# MQ-135_Matheus_Rossetti_-_14205347.net
KiCad netlist of a schematic drawn in EAGLE
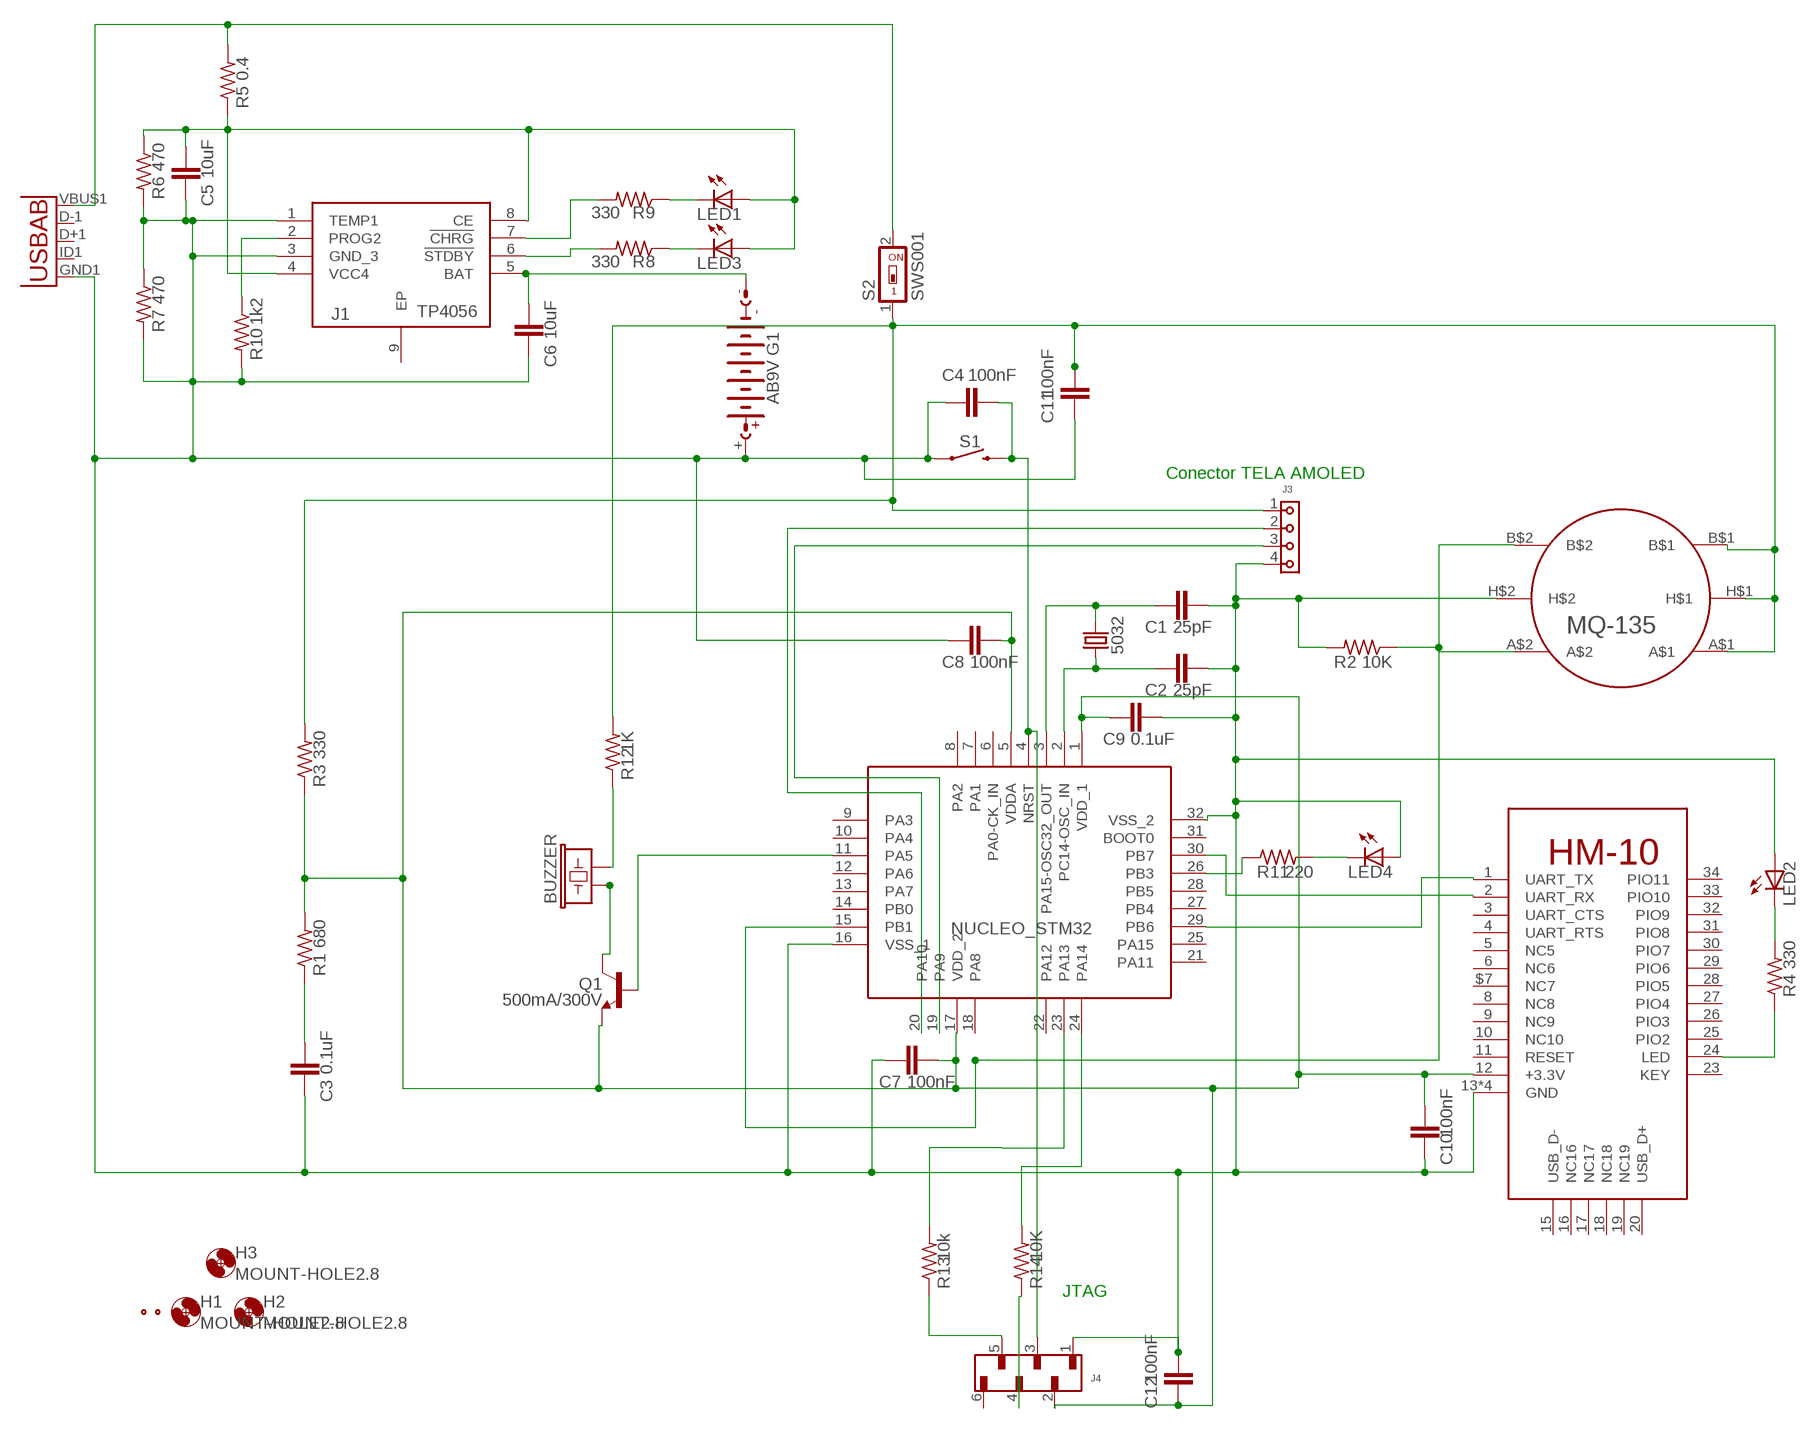
[diagram p0: schematic, sheet 1]

(export (version "E")
  (design (tool "Eeschema 10.0.6"))
  (components
    (comp (ref "BT_SENSOR")
      (value "HM-10-BOARD")
      (footprint "eagle-import:26.9X13X2.2_BOARD")
      (libsource (lib "eagle-import") (part "HM-10-BOARD"))
    )
    (comp (ref "C1")
      (value "25pF")
      (footprint "eagle-import:CAP_0805")
      (fields
        (field (name "DIGIKEY_PART_NUMBER") "311-1140-2-ND")
        (field (name "MANUFACTURER") "Yageo")
        (field (name "MPN") "CC0805KRX7R9BB104")
        (field (name "CREATED_BY") "PCBLayout.com")
      )
      (libsource (lib "eagle-import") (part "CC0805KRX7R9BB104"))
    )
    (comp (ref "C2")
      (value "25pF")
      (footprint "eagle-import:CAP_0805")
      (fields
        (field (name "DIGIKEY_PART_NUMBER") "311-1140-2-ND")
        (field (name "MANUFACTURER") "Yageo")
        (field (name "MPN") "CC0805KRX7R9BB104")
        (field (name "CREATED_BY") "PCBLayout.com")
      )
      (libsource (lib "eagle-import") (part "CC0805KRX7R9BB104"))
    )
    (comp (ref "C3")
      (value "0.1uF")
      (footprint "eagle-import:CAP_0805")
      (fields
        (field (name "DIGIKEY_PART_NUMBER") "311-1140-2-ND")
        (field (name "MANUFACTURER") "Yageo")
        (field (name "MPN") "CC0805KRX7R9BB104")
        (field (name "CREATED_BY") "PCBLayout.com")
      )
      (libsource (lib "eagle-import") (part "CC0805KRX7R9BB104"))
    )
    (comp (ref "C4")
      (value "100nF")
      (footprint "eagle-import:CAP_0805")
      (fields
        (field (name "DIGIKEY_PART_NUMBER") "311-1140-2-ND")
        (field (name "MANUFACTURER") "Yageo")
        (field (name "MPN") "CC0805KRX7R9BB104")
        (field (name "CREATED_BY") "PCBLayout.com")
      )
      (libsource (lib "eagle-import") (part "CC0805KRX7R9BB104"))
    )
    (comp (ref "C5")
      (value "10uF")
      (footprint "eagle-import:CAP_0805")
      (fields
        (field (name "DIGIKEY_PART_NUMBER") "311-1140-2-ND")
        (field (name "MANUFACTURER") "Yageo")
        (field (name "MPN") "CC0805KRX7R9BB104")
        (field (name "CREATED_BY") "PCBLayout.com")
      )
      (libsource (lib "eagle-import") (part "CC0805KRX7R9BB104"))
    )
    (comp (ref "C6")
      (value "10uF")
      (footprint "eagle-import:CAP_0805")
      (fields
        (field (name "DIGIKEY_PART_NUMBER") "311-1140-2-ND")
        (field (name "MANUFACTURER") "Yageo")
        (field (name "MPN") "CC0805KRX7R9BB104")
        (field (name "CREATED_BY") "PCBLayout.com")
      )
      (libsource (lib "eagle-import") (part "CC0805KRX7R9BB104"))
    )
    (comp (ref "C7")
      (value "100nF")
      (footprint "eagle-import:CAP_0805")
      (fields
        (field (name "DIGIKEY_PART_NUMBER") "311-1140-2-ND")
        (field (name "MANUFACTURER") "Yageo")
        (field (name "MPN") "CC0805KRX7R9BB104")
        (field (name "CREATED_BY") "PCBLayout.com")
      )
      (libsource (lib "eagle-import") (part "CC0805KRX7R9BB104"))
    )
    (comp (ref "C8")
      (value "100nF")
      (footprint "eagle-import:CAP_0805")
      (fields
        (field (name "DIGIKEY_PART_NUMBER") "311-1140-2-ND")
        (field (name "MANUFACTURER") "Yageo")
        (field (name "MPN") "CC0805KRX7R9BB104")
        (field (name "CREATED_BY") "PCBLayout.com")
      )
      (libsource (lib "eagle-import") (part "CC0805KRX7R9BB104"))
    )
    (comp (ref "C9")
      (value "0.1uF")
      (footprint "eagle-import:CAP_0805")
      (fields
        (field (name "DIGIKEY_PART_NUMBER") "311-1140-2-ND")
        (field (name "MANUFACTURER") "Yageo")
        (field (name "MPN") "CC0805KRX7R9BB104")
        (field (name "CREATED_BY") "PCBLayout.com")
      )
      (libsource (lib "eagle-import") (part "CC0805KRX7R9BB104"))
    )
    (comp (ref "C10")
      (value "100nF")
      (footprint "eagle-import:CAP_0805")
      (fields
        (field (name "DIGIKEY_PART_NUMBER") "311-1140-2-ND")
        (field (name "MANUFACTURER") "Yageo")
        (field (name "MPN") "CC0805KRX7R9BB104")
        (field (name "CREATED_BY") "PCBLayout.com")
      )
      (libsource (lib "eagle-import") (part "CC0805KRX7R9BB104"))
    )
    (comp (ref "C11")
      (value "100nF")
      (footprint "eagle-import:CAP_0805")
      (fields
        (field (name "DIGIKEY_PART_NUMBER") "311-1140-2-ND")
        (field (name "MANUFACTURER") "Yageo")
        (field (name "MPN") "CC0805KRX7R9BB104")
        (field (name "CREATED_BY") "PCBLayout.com")
      )
      (libsource (lib "eagle-import") (part "CC0805KRX7R9BB104"))
    )
    (comp (ref "C12")
      (value "100nF")
      (footprint "eagle-import:CAP_0805")
      (fields
        (field (name "DIGIKEY_PART_NUMBER") "311-1140-2-ND")
        (field (name "MANUFACTURER") "Yageo")
        (field (name "MPN") "CC0805KRX7R9BB104")
        (field (name "CREATED_BY") "PCBLayout.com")
      )
      (libsource (lib "eagle-import") (part "CC0805KRX7R9BB104"))
    )
    (comp (ref "G1")
      (value "AB9V")
      (footprint "eagle-import:AB9V")
      (libsource (lib "eagle-import") (part "AB9V"))
    )
    (comp (ref "H1")
      (value "MOUNT-HOLE2.8")
      (footprint "eagle-import:2,8")
      (libsource (lib "eagle-import") (part "MOUNT-HOLE2.8"))
    )
    (comp (ref "H2")
      (value "MOUNT-HOLE2.8")
      (footprint "eagle-import:2,8")
      (libsource (lib "eagle-import") (part "MOUNT-HOLE2.8"))
    )
    (comp (ref "H3")
      (value "MOUNT-HOLE2.8")
      (footprint "eagle-import:2,8")
      (libsource (lib "eagle-import") (part "MOUNT-HOLE2.8"))
    )
    (comp (ref "J1")
      (value "TP4056")
      (footprint "eagle-import:SOIC127P600X175-9N")
      (libsource (lib "eagle-import") (part "TP4056"))
    )
    (comp (ref "J3")
      (value "6130XX11821_61300411821")
      (footprint "eagle-import:61300411821")
      (libsource (lib "eagle-import") (part "6130XX11821_61300411821"))
    )
    (comp (ref "J4")
      (value "6100XX18221_61000618221")
      (footprint "eagle-import:61000618221")
      (libsource (lib "eagle-import") (part "6100XX18221_61000618221"))
    )
    (comp (ref "LED1")
      (value "LEDCHIP-LED0805")
      (footprint "eagle-import:CHIP-LED0805")
      (libsource (lib "eagle-import") (part "LEDCHIP-LED0805"))
    )
    (comp (ref "LED2")
      (value "LEDCHIP-LED0805")
      (footprint "eagle-import:CHIP-LED0805")
      (libsource (lib "eagle-import") (part "LEDCHIP-LED0805"))
    )
    (comp (ref "LED3")
      (value "LEDCHIP-LED0805")
      (footprint "eagle-import:CHIP-LED0805")
      (libsource (lib "eagle-import") (part "LEDCHIP-LED0805"))
    )
    (comp (ref "LED4")
      (value "LEDCHIP-LED0805")
      (footprint "eagle-import:CHIP-LED0805")
      (libsource (lib "eagle-import") (part "LEDCHIP-LED0805"))
    )
    (comp (ref "LS4")
      (value "BUZZER")
      (footprint "eagle-import:BUZZER-CCV-KIT")
      (libsource (lib "eagle-import") (part "BUZZER-SMD_KIT"))
    )
    (comp (ref "NUCLEO_STM32")
      (value "STM32")
      (footprint "eagle-import:QFP80P900X900X160-32N")
      (fields
        (field (name "ARROW_PART_NUMBER") "STM32L031K6T6TR")
        (field (name "MOUSER_PART_NUMBER") "511-STM32L031K6T6TR")
      )
      (libsource (lib "eagle-import") (part "STM32L031K6T6TR"))
    )
    (comp (ref "Q1")
      (value "500mA/300V")
      (footprint "eagle-import:SOT23-3")
      (libsource (lib "eagle-import") (part "TRANS_NPN-MMBTA42"))
    )
    (comp (ref "R1")
      (value "680")
      (footprint "eagle-import:RES_0805")
      (fields
        (field (name "DIGIKEY_PART_NUMBER") "541-0.0ATR-ND")
        (field (name "MANUFACTURER") "Vishay Dale")
        (field (name "MPN") "CRCW08050000Z0EA")
        (field (name "CREATED_BY") "PCBLayout.com")
      )
      (libsource (lib "eagle-import") (part "CRCW08050000Z0EA"))
    )
    (comp (ref "R2")
      (value "10K")
      (footprint "eagle-import:RES_0805")
      (fields
        (field (name "DIGIKEY_PART_NUMBER") "541-0.0ATR-ND")
        (field (name "MANUFACTURER") "Vishay Dale")
        (field (name "MPN") "CRCW08050000Z0EA")
        (field (name "CREATED_BY") "PCBLayout.com")
      )
      (libsource (lib "eagle-import") (part "CRCW08050000Z0EA"))
    )
    (comp (ref "R3")
      (value "330")
      (footprint "eagle-import:RES_0805")
      (fields
        (field (name "DIGIKEY_PART_NUMBER") "541-0.0ATR-ND")
        (field (name "MANUFACTURER") "Vishay Dale")
        (field (name "MPN") "CRCW08050000Z0EA")
        (field (name "CREATED_BY") "PCBLayout.com")
      )
      (libsource (lib "eagle-import") (part "CRCW08050000Z0EA"))
    )
    (comp (ref "R4")
      (value "330")
      (footprint "eagle-import:RES_0805")
      (fields
        (field (name "DIGIKEY_PART_NUMBER") "541-0.0ATR-ND")
        (field (name "MANUFACTURER") "Vishay Dale")
        (field (name "MPN") "CRCW08050000Z0EA")
        (field (name "CREATED_BY") "PCBLayout.com")
      )
      (libsource (lib "eagle-import") (part "CRCW08050000Z0EA"))
    )
    (comp (ref "R5")
      (value "0.4")
      (footprint "eagle-import:RES_0805")
      (fields
        (field (name "DIGIKEY_PART_NUMBER") "541-0.0ATR-ND")
        (field (name "MANUFACTURER") "Vishay Dale")
        (field (name "MPN") "CRCW08050000Z0EA")
        (field (name "CREATED_BY") "PCBLayout.com")
      )
      (libsource (lib "eagle-import") (part "CRCW08050000Z0EA"))
    )
    (comp (ref "R6")
      (value "470")
      (footprint "eagle-import:RES_0805")
      (fields
        (field (name "DIGIKEY_PART_NUMBER") "541-0.0ATR-ND")
        (field (name "MANUFACTURER") "Vishay Dale")
        (field (name "MPN") "CRCW08050000Z0EA")
        (field (name "CREATED_BY") "PCBLayout.com")
      )
      (libsource (lib "eagle-import") (part "CRCW08050000Z0EA"))
    )
    (comp (ref "R7")
      (value "470")
      (footprint "eagle-import:RES_0805")
      (fields
        (field (name "DIGIKEY_PART_NUMBER") "541-0.0ATR-ND")
        (field (name "MANUFACTURER") "Vishay Dale")
        (field (name "MPN") "CRCW08050000Z0EA")
        (field (name "CREATED_BY") "PCBLayout.com")
      )
      (libsource (lib "eagle-import") (part "CRCW08050000Z0EA"))
    )
    (comp (ref "R8")
      (value "330")
      (footprint "eagle-import:RES_0805")
      (fields
        (field (name "DIGIKEY_PART_NUMBER") "541-0.0ATR-ND")
        (field (name "MANUFACTURER") "Vishay Dale")
        (field (name "MPN") "CRCW08050000Z0EA")
        (field (name "SPICEPREFIX") "R")
        (field (name "CREATED_BY") "PCBLayout.com")
      )
      (libsource (lib "eagle-import") (part "CRCW08050000Z0EA"))
    )
    (comp (ref "R9")
      (value "330")
      (footprint "eagle-import:RES_0805")
      (fields
        (field (name "DIGIKEY_PART_NUMBER") "541-0.0ATR-ND")
        (field (name "MANUFACTURER") "Vishay Dale")
        (field (name "MPN") "CRCW08050000Z0EA")
        (field (name "SPICEPREFIX") "R")
        (field (name "CREATED_BY") "PCBLayout.com")
      )
      (libsource (lib "eagle-import") (part "CRCW08050000Z0EA"))
    )
    (comp (ref "R10")
      (value "1k2")
      (footprint "eagle-import:RES_0805")
      (fields
        (field (name "DIGIKEY_PART_NUMBER") "541-0.0ATR-ND")
        (field (name "MANUFACTURER") "Vishay Dale")
        (field (name "MPN") "CRCW08050000Z0EA")
        (field (name "CREATED_BY") "PCBLayout.com")
      )
      (libsource (lib "eagle-import") (part "CRCW08050000Z0EA"))
    )
    (comp (ref "R11")
      (value "220")
      (footprint "eagle-import:RES_0805")
      (fields
        (field (name "DIGIKEY_PART_NUMBER") "541-0.0ATR-ND")
        (field (name "MANUFACTURER") "Vishay Dale")
        (field (name "MPN") "CRCW08050000Z0EA")
        (field (name "CREATED_BY") "PCBLayout.com")
      )
      (libsource (lib "eagle-import") (part "CRCW08050000Z0EA"))
    )
    (comp (ref "R12")
      (value "1K")
      (footprint "eagle-import:RES_0805")
      (fields
        (field (name "DIGIKEY_PART_NUMBER") "541-0.0ATR-ND")
        (field (name "MANUFACTURER") "Vishay Dale")
        (field (name "MPN") "CRCW08050000Z0EA")
        (field (name "CREATED_BY") "PCBLayout.com")
      )
      (libsource (lib "eagle-import") (part "CRCW08050000Z0EA"))
    )
    (comp (ref "R13")
      (value "10k")
      (footprint "eagle-import:RES_0805")
      (fields
        (field (name "DIGIKEY_PART_NUMBER") "541-0.0ATR-ND")
        (field (name "MANUFACTURER") "Vishay Dale")
        (field (name "MPN") "CRCW08050000Z0EA")
        (field (name "CREATED_BY") "PCBLayout.com")
      )
      (libsource (lib "eagle-import") (part "CRCW08050000Z0EA"))
    )
    (comp (ref "R14")
      (value "10K")
      (footprint "eagle-import:RES_0805")
      (fields
        (field (name "DIGIKEY_PART_NUMBER") "541-0.0ATR-ND")
        (field (name "MANUFACTURER") "Vishay Dale")
        (field (name "MPN") "CRCW08050000Z0EA")
        (field (name "CREATED_BY") "PCBLayout.com")
      )
      (libsource (lib "eagle-import") (part "CRCW08050000Z0EA"))
    )
    (comp (ref "S1")
      (value "MOMENTARY-SWITCH-SPST-SMD-6.0X3.5MM")
      (footprint "eagle-import:TACTILE_SWITCH_SMD_6.0X3.5MM")
      (libsource (lib "eagle-import") (part "MOMENTARY-SWITCH-SPST-SMD-6.0X3.5MM"))
    )
    (comp (ref "S2")
      (value "SWS001")
      (footprint "eagle-import:SMS-001")
      (libsource (lib "eagle-import") (part "SWS001"))
    )
    (comp (ref "U$1")
      (value "MQ_135_A")
      (footprint "eagle-import:MQ-135")
      (libsource (lib "eagle-import") (part "MQ_135_A"))
    )
    (comp (ref "U1")
      (value "USB\"\"")
      (footprint "eagle-import:USB-MICRO-SMD")
      (libsource (lib "eagle-import") (part "USB{dblquote}{dblquote}"))
    )
    (comp (ref "X1")
      (value "FIDUCIAL_0.6-1.2MM")
      (footprint "eagle-import:FIDUCIAL0.6-1.2")
      (libsource (lib "eagle-import") (part "FIDUCIAL_0.6-1.2MM"))
    )
    (comp (ref "X2")
      (value "5032")
      (footprint "eagle-import:5032_2P")
      (fields
        (field (name "MANUFACTURER") "Xinhunjing")
        (field (name "MPN") "5032/2P")
        (field (name "CREATED_BY") "PCBLayout.com")
      )
      (libsource (lib "eagle-import") (part "5032/2P"))
    )
    (comp (ref "X3")
      (value "FIDUCIAL_0.6-1.2MM")
      (footprint "eagle-import:FIDUCIAL0.6-1.2")
      (libsource (lib "eagle-import") (part "FIDUCIAL_0.6-1.2MM"))
    )
  )
  (nets
    (net (code "1") (name "Net-(BT_SENSOR-+3.3V)") (class "Default")
      (node (ref "BT_SENSOR") (pin "12") (pinfunction "+3.3V_12") (pintype "bidirectional"))
      (node (ref "C10") (pin "1") (pinfunction "1_1") (pintype "passive"))
      (node (ref "C12") (pin "1") (pinfunction "1_1") (pintype "passive"))
      (node (ref "C7") (pin "1") (pinfunction "1_1") (pintype "passive"))
      (node (ref "C8") (pin "1") (pinfunction "1_1") (pintype "passive"))
      (node (ref "C9") (pin "2") (pinfunction "2_2") (pintype "passive"))
      (node (ref "J4") (pin "2") (pinfunction "2_2") (pintype "passive"))
      (node (ref "NUCLEO_STM32") (pin "1") (pinfunction "VDD_1_1") (pintype "bidirectional"))
      (node (ref "NUCLEO_STM32") (pin "17") (pinfunction "VDD_2_17") (pintype "bidirectional"))
      (node (ref "NUCLEO_STM32") (pin "5") (pinfunction "VDDA_5") (pintype "bidirectional"))
      (node (ref "Q1") (pin "2") (pinfunction "E_2") (pintype "passive"))
      (node (ref "R1") (pin "2") (pinfunction "2_2") (pintype "passive"))
      (node (ref "R3") (pin "1") (pinfunction "1_1") (pintype "passive"))
    )
    (net (code "2") (name "Net-(BT_SENSOR-LED)") (class "Default")
      (node (ref "BT_SENSOR") (pin "24") (pinfunction "LED_24") (pintype "bidirectional"))
      (node (ref "R4") (pin "1") (pinfunction "1_1") (pintype "passive"))
    )
    (net (code "3") (name "Net-(BT_SENSOR-UART_RX)") (class "Default")
      (node (ref "BT_SENSOR") (pin "2") (pinfunction "UART_RX_2") (pintype "bidirectional"))
      (node (ref "NUCLEO_STM32") (pin "30") (pinfunction "PB7_30") (pintype "bidirectional"))
    )
    (net (code "4") (name "Net-(BT_SENSOR-UART_TX)") (class "Default")
      (node (ref "BT_SENSOR") (pin "1") (pinfunction "UART_TX_1") (pintype "bidirectional"))
      (node (ref "NUCLEO_STM32") (pin "29") (pinfunction "PB6_29") (pintype "bidirectional"))
    )
    (net (code "5") (name "Net-(C3-Pad1)") (class "Default")
      (node (ref "C3") (pin "1") (pinfunction "1_1") (pintype "passive"))
      (node (ref "R1") (pin "1") (pinfunction "1_1") (pintype "passive"))
    )
    (net (code "6") (name "Net-(C11-Pad2)") (class "Default")
      (node (ref "C11") (pin "2") (pinfunction "2_2") (pintype "passive"))
      (node (ref "J3") (pin "1") (pinfunction "1_1") (pintype "passive"))
      (node (ref "R12") (pin "2") (pinfunction "2_2") (pintype "passive"))
      (node (ref "R3") (pin "2") (pinfunction "2_2") (pintype "passive"))
      (node (ref "S2") (pin "1") (pinfunction "1_1") (pintype "passive"))
      (node (ref "U$1") (pin "A$1") (pinfunction "A$1_A$1") (pintype "bidirectional"))
      (node (ref "U$1") (pin "B$1") (pinfunction "B$1_B$1") (pintype "bidirectional"))
      (node (ref "U$1") (pin "H$1") (pinfunction "H$1_H$1") (pintype "bidirectional"))
    )
    (net (code "7") (name "Net-(J1-BAT)") (class "Default")
      (node (ref "C6") (pin "2") (pinfunction "2_2") (pintype "passive"))
      (node (ref "G1") (pin "-") (pinfunction "-_-") (pintype "passive"))
      (node (ref "J1") (pin "5") (pinfunction "BAT_5") (pintype "bidirectional"))
    )
    (net (code "8") (name "Net-(J1-CE)") (class "Default")
      (node (ref "C5") (pin "1") (pinfunction "1_1") (pintype "passive"))
      (node (ref "J1") (pin "4") (pinfunction "VCC4_4") (pintype "bidirectional"))
      (node (ref "J1") (pin "8") (pinfunction "CE_8") (pintype "bidirectional"))
      (node (ref "LED1") (pin "A") (pinfunction "A_A") (pintype "passive"))
      (node (ref "LED3") (pin "A") (pinfunction "A_A") (pintype "passive"))
      (node (ref "R5") (pin "1") (pinfunction "1_1") (pintype "passive"))
      (node (ref "R6") (pin "1") (pinfunction "1_1") (pintype "passive"))
    )
    (net (code "9") (name "Net-(J1-GND_3)") (class "Default")
      (node (ref "BT_SENSOR") (pin "13") (pinfunction "GND_13") (pintype "bidirectional"))
      (node (ref "BT_SENSOR") (pin "14") (pinfunction "GND_14") (pintype "bidirectional"))
      (node (ref "BT_SENSOR") (pin "21") (pinfunction "GND_21") (pintype "bidirectional"))
      (node (ref "BT_SENSOR") (pin "22") (pinfunction "GND_22") (pintype "bidirectional"))
      (node (ref "C1") (pin "2") (pinfunction "2_2") (pintype "passive"))
      (node (ref "C10") (pin "2") (pinfunction "2_2") (pintype "passive"))
      (node (ref "C11") (pin "1") (pinfunction "1_1") (pintype "passive"))
      (node (ref "C12") (pin "2") (pinfunction "2_2") (pintype "passive"))
      (node (ref "C2") (pin "2") (pinfunction "2_2") (pintype "passive"))
      (node (ref "C3") (pin "2") (pinfunction "2_2") (pintype "passive"))
      (node (ref "C4") (pin "1") (pinfunction "1_1") (pintype "passive"))
      (node (ref "C5") (pin "2") (pinfunction "2_2") (pintype "passive"))
      (node (ref "C6") (pin "1") (pinfunction "1_1") (pintype "passive"))
      (node (ref "C7") (pin "2") (pinfunction "2_2") (pintype "passive"))
      (node (ref "C8") (pin "2") (pinfunction "2_2") (pintype "passive"))
      (node (ref "C9") (pin "1") (pinfunction "1_1") (pintype "passive"))
      (node (ref "G1") (pin "+") (pinfunction "+_+") (pintype "passive"))
      (node (ref "J1") (pin "1") (pinfunction "TEMP1_1") (pintype "bidirectional"))
      (node (ref "J1") (pin "3") (pinfunction "GND_3_3") (pintype "bidirectional"))
      (node (ref "J3") (pin "4") (pinfunction "4_4") (pintype "passive"))
      (node (ref "J4") (pin "1") (pinfunction "1_1") (pintype "passive"))
      (node (ref "LED2") (pin "A") (pinfunction "A_A") (pintype "passive"))
      (node (ref "LED4") (pin "A") (pinfunction "A_A") (pintype "passive"))
      (node (ref "NUCLEO_STM32") (pin "16") (pinfunction "VSS_1_16") (pintype "bidirectional"))
      (node (ref "NUCLEO_STM32") (pin "32") (pinfunction "VSS_2_32") (pintype "bidirectional"))
      (node (ref "R10") (pin "2") (pinfunction "2_2") (pintype "passive"))
      (node (ref "R2") (pin "2") (pinfunction "2_2") (pintype "passive"))
      (node (ref "R6") (pin "2") (pinfunction "2_2") (pintype "passive"))
      (node (ref "R7") (pin "1") (pinfunction "1_1") (pintype "passive"))
      (node (ref "R7") (pin "2") (pinfunction "2_2") (pintype "passive"))
      (node (ref "S1") (pin "1") (pinfunction "1_1") (pintype "passive"))
      (node (ref "U$1") (pin "H$2") (pinfunction "H$2_H$2") (pintype "bidirectional"))
      (node (ref "U1") (pin "GND1") (pinfunction "GND_GND1") (pintype "bidirectional"))
    )
    (net (code "10") (name "Net-(J1-PROG2)") (class "Default")
      (node (ref "J1") (pin "2") (pinfunction "PROG2_2") (pintype "bidirectional"))
      (node (ref "R10") (pin "1") (pinfunction "1_1") (pintype "passive"))
    )
    (net (code "11") (name "Net-(J1-~{CHRG})") (class "Default")
      (node (ref "J1") (pin "7") (pinfunction "~{CHRG}_7") (pintype "bidirectional"))
      (node (ref "R9") (pin "2") (pinfunction "2_2") (pintype "passive"))
    )
    (net (code "12") (name "Net-(J1-~{STDBY})") (class "Default")
      (node (ref "J1") (pin "6") (pinfunction "~{STDBY}_6") (pintype "bidirectional"))
      (node (ref "R8") (pin "2") (pinfunction "2_2") (pintype "passive"))
    )
    (net (code "13") (name "Net-(J4-Pad4)") (class "Default")
      (node (ref "J4") (pin "4") (pinfunction "4_4") (pintype "passive"))
      (node (ref "R14") (pin "1") (pinfunction "1_1") (pintype "passive"))
    )
    (net (code "14") (name "Net-(J4-Pad5)") (class "Default")
      (node (ref "J4") (pin "5") (pinfunction "5_5") (pintype "passive"))
      (node (ref "R13") (pin "1") (pinfunction "1_1") (pintype "passive"))
    )
    (net (code "15") (name "Net-(LED1-PadC)") (class "Default")
      (node (ref "LED1") (pin "C") (pinfunction "C_C") (pintype "passive"))
      (node (ref "R9") (pin "1") (pinfunction "1_1") (pintype "passive"))
    )
    (net (code "16") (name "Net-(LED2-PadC)") (class "Default")
      (node (ref "LED2") (pin "C") (pinfunction "C_C") (pintype "passive"))
      (node (ref "R4") (pin "2") (pinfunction "2_2") (pintype "passive"))
    )
    (net (code "17") (name "Net-(LED3-PadC)") (class "Default")
      (node (ref "LED3") (pin "C") (pinfunction "C_C") (pintype "passive"))
      (node (ref "R8") (pin "1") (pinfunction "1_1") (pintype "passive"))
    )
    (net (code "18") (name "Net-(LED4-PadC)") (class "Default")
      (node (ref "LED4") (pin "C") (pinfunction "C_C") (pintype "passive"))
      (node (ref "R11") (pin "2") (pinfunction "2_2") (pintype "passive"))
    )
    (net (code "19") (name "Net-(LS4-1)") (class "Default")
      (node (ref "LS4") (pin "+") (pinfunction "1_+") (pintype "passive"))
      (node (ref "Q1") (pin "3") (pinfunction "C_3") (pintype "passive"))
    )
    (net (code "20") (name "Net-(LS4-2)") (class "Default")
      (node (ref "LS4") (pin "-") (pinfunction "2_-") (pintype "passive"))
      (node (ref "R12") (pin "1") (pinfunction "1_1") (pintype "passive"))
    )
    (net (code "21") (name "Net-(NUCLEO_STM32-NRST)") (class "Default")
      (node (ref "C4") (pin "2") (pinfunction "2_2") (pintype "passive"))
      (node (ref "J4") (pin "3") (pinfunction "3_3") (pintype "passive"))
      (node (ref "NUCLEO_STM32") (pin "4") (pinfunction "NRST_4") (pintype "bidirectional"))
      (node (ref "S1") (pin "2") (pinfunction "2_2") (pintype "passive"))
    )
    (net (code "22") (name "Net-(NUCLEO_STM32-PA5)") (class "Default")
      (node (ref "NUCLEO_STM32") (pin "11") (pinfunction "PA5_11") (pintype "bidirectional"))
      (node (ref "Q1") (pin "1") (pinfunction "B_1") (pintype "passive"))
    )
    (net (code "23") (name "Net-(NUCLEO_STM32-PA9)") (class "Default")
      (node (ref "J3") (pin "3") (pinfunction "3_3") (pintype "passive"))
      (node (ref "NUCLEO_STM32") (pin "19") (pinfunction "PA9_19") (pintype "bidirectional"))
    )
    (net (code "24") (name "Net-(NUCLEO_STM32-PA10)") (class "Default")
      (node (ref "J3") (pin "2") (pinfunction "2_2") (pintype "passive"))
      (node (ref "NUCLEO_STM32") (pin "20") (pinfunction "PA10_20") (pintype "bidirectional"))
    )
    (net (code "25") (name "Net-(NUCLEO_STM32-PA13)") (class "Default")
      (node (ref "NUCLEO_STM32") (pin "23") (pinfunction "PA13_23") (pintype "bidirectional"))
      (node (ref "R13") (pin "2") (pinfunction "2_2") (pintype "passive"))
    )
    (net (code "26") (name "Net-(NUCLEO_STM32-PA14)") (class "Default")
      (node (ref "NUCLEO_STM32") (pin "24") (pinfunction "PA14_24") (pintype "bidirectional"))
      (node (ref "R14") (pin "2") (pinfunction "2_2") (pintype "passive"))
    )
    (net (code "27") (name "Net-(NUCLEO_STM32-PA15-OSC32_OUT)") (class "Default")
      (node (ref "C1") (pin "1") (pinfunction "1_1") (pintype "passive"))
      (node (ref "NUCLEO_STM32") (pin "3") (pinfunction "PA15-OSC32_OUT_3") (pintype "bidirectional"))
      (node (ref "X2") (pin "2") (pinfunction "2_2") (pintype "passive"))
    )
    (net (code "28") (name "Net-(NUCLEO_STM32-PB1)") (class "Default")
      (node (ref "NUCLEO_STM32") (pin "15") (pinfunction "PB1_15") (pintype "bidirectional"))
      (node (ref "R2") (pin "1") (pinfunction "1_1") (pintype "passive"))
      (node (ref "U$1") (pin "A$2") (pinfunction "A$2_A$2") (pintype "bidirectional"))
      (node (ref "U$1") (pin "B$2") (pinfunction "B$2_B$2") (pintype "bidirectional"))
    )
    (net (code "29") (name "Net-(NUCLEO_STM32-PB3)") (class "Default")
      (node (ref "NUCLEO_STM32") (pin "26") (pinfunction "PB3_26") (pintype "bidirectional"))
      (node (ref "R11") (pin "1") (pinfunction "1_1") (pintype "passive"))
    )
    (net (code "30") (name "Net-(NUCLEO_STM32-PC14-OSC_IN)") (class "Default")
      (node (ref "C2") (pin "1") (pinfunction "1_1") (pintype "passive"))
      (node (ref "NUCLEO_STM32") (pin "2") (pinfunction "PC14-OSC_IN_2") (pintype "bidirectional"))
      (node (ref "X2") (pin "1") (pinfunction "1_1") (pintype "passive"))
    )
    (net (code "31") (name "Net-(U1-VBUS)") (class "Default")
      (node (ref "R5") (pin "2") (pinfunction "2_2") (pintype "passive"))
      (node (ref "S2") (pin "2") (pinfunction "2_2") (pintype "passive"))
      (node (ref "U1") (pin "VBUS1") (pinfunction "VBUS_VBUS1") (pintype "bidirectional"))
    )
    (net (code "32") (name "unconnected-(BT_SENSOR-KEY-Pad23)") (class "Default")
      (node (ref "BT_SENSOR") (pin "23") (pinfunction "KEY_23") (pintype "bidirectional"))
    )
    (net (code "33") (name "unconnected-(BT_SENSOR-NC5-Pad5)") (class "Default")
      (node (ref "BT_SENSOR") (pin "5") (pinfunction "NC5_5") (pintype "bidirectional"))
    )
    (net (code "34") (name "unconnected-(BT_SENSOR-NC6-Pad6)") (class "Default")
      (node (ref "BT_SENSOR") (pin "6") (pinfunction "NC6_6") (pintype "bidirectional"))
    )
    (net (code "35") (name "unconnected-(BT_SENSOR-NC7-Pad$7)") (class "Default")
      (node (ref "BT_SENSOR") (pin "$7") (pinfunction "NC7_$7") (pintype "bidirectional"))
    )
    (net (code "36") (name "unconnected-(BT_SENSOR-NC8-Pad8)") (class "Default")
      (node (ref "BT_SENSOR") (pin "8") (pinfunction "NC8_8") (pintype "bidirectional"))
    )
    (net (code "37") (name "unconnected-(BT_SENSOR-NC9-Pad9)") (class "Default")
      (node (ref "BT_SENSOR") (pin "9") (pinfunction "NC9_9") (pintype "bidirectional"))
    )
    (net (code "38") (name "unconnected-(BT_SENSOR-NC10-Pad10)") (class "Default")
      (node (ref "BT_SENSOR") (pin "10") (pinfunction "NC10_10") (pintype "bidirectional"))
    )
    (net (code "39") (name "unconnected-(BT_SENSOR-NC16-Pad16)") (class "Default")
      (node (ref "BT_SENSOR") (pin "16") (pinfunction "NC16_16") (pintype "bidirectional"))
    )
    (net (code "40") (name "unconnected-(BT_SENSOR-NC17-Pad17)") (class "Default")
      (node (ref "BT_SENSOR") (pin "17") (pinfunction "NC17_17") (pintype "bidirectional"))
    )
    (net (code "41") (name "unconnected-(BT_SENSOR-NC18-Pad18)") (class "Default")
      (node (ref "BT_SENSOR") (pin "18") (pinfunction "NC18_18") (pintype "bidirectional"))
    )
    (net (code "42") (name "unconnected-(BT_SENSOR-NC19-Pad19)") (class "Default")
      (node (ref "BT_SENSOR") (pin "19") (pinfunction "NC19_19") (pintype "bidirectional"))
    )
    (net (code "43") (name "unconnected-(BT_SENSOR-PIO2-Pad25)") (class "Default")
      (node (ref "BT_SENSOR") (pin "25") (pinfunction "PIO2_25") (pintype "bidirectional"))
    )
    (net (code "44") (name "unconnected-(BT_SENSOR-PIO3-Pad26)") (class "Default")
      (node (ref "BT_SENSOR") (pin "26") (pinfunction "PIO3_26") (pintype "bidirectional"))
    )
    (net (code "45") (name "unconnected-(BT_SENSOR-PIO4-Pad27)") (class "Default")
      (node (ref "BT_SENSOR") (pin "27") (pinfunction "PIO4_27") (pintype "bidirectional"))
    )
    (net (code "46") (name "unconnected-(BT_SENSOR-PIO5-Pad28)") (class "Default")
      (node (ref "BT_SENSOR") (pin "28") (pinfunction "PIO5_28") (pintype "bidirectional"))
    )
    (net (code "47") (name "unconnected-(BT_SENSOR-PIO6-Pad29)") (class "Default")
      (node (ref "BT_SENSOR") (pin "29") (pinfunction "PIO6_29") (pintype "bidirectional"))
    )
    (net (code "48") (name "unconnected-(BT_SENSOR-PIO7-Pad30)") (class "Default")
      (node (ref "BT_SENSOR") (pin "30") (pinfunction "PIO7_30") (pintype "bidirectional"))
    )
    (net (code "49") (name "unconnected-(BT_SENSOR-PIO8-Pad31)") (class "Default")
      (node (ref "BT_SENSOR") (pin "31") (pinfunction "PIO8_31") (pintype "bidirectional"))
    )
    (net (code "50") (name "unconnected-(BT_SENSOR-PIO9-Pad32)") (class "Default")
      (node (ref "BT_SENSOR") (pin "32") (pinfunction "PIO9_32") (pintype "bidirectional"))
    )
    (net (code "51") (name "unconnected-(BT_SENSOR-PIO10-Pad33)") (class "Default")
      (node (ref "BT_SENSOR") (pin "33") (pinfunction "PIO10_33") (pintype "bidirectional"))
    )
    (net (code "52") (name "unconnected-(BT_SENSOR-PIO11-Pad34)") (class "Default")
      (node (ref "BT_SENSOR") (pin "34") (pinfunction "PIO11_34") (pintype "bidirectional"))
    )
    (net (code "53") (name "unconnected-(BT_SENSOR-RESET-Pad11)") (class "Default")
      (node (ref "BT_SENSOR") (pin "11") (pinfunction "RESET_11") (pintype "bidirectional"))
    )
    (net (code "54") (name "unconnected-(BT_SENSOR-UART_CTS-Pad3)") (class "Default")
      (node (ref "BT_SENSOR") (pin "3") (pinfunction "UART_CTS_3") (pintype "bidirectional"))
    )
    (net (code "55") (name "unconnected-(BT_SENSOR-UART_RTS-Pad4)") (class "Default")
      (node (ref "BT_SENSOR") (pin "4") (pinfunction "UART_RTS_4") (pintype "bidirectional"))
    )
    (net (code "56") (name "unconnected-(BT_SENSOR-USB_D+-Pad20)") (class "Default")
      (node (ref "BT_SENSOR") (pin "20") (pinfunction "USB_D+_20") (pintype "bidirectional"))
    )
    (net (code "57") (name "unconnected-(BT_SENSOR-USB_D--Pad15)") (class "Default")
      (node (ref "BT_SENSOR") (pin "15") (pinfunction "USB_D-_15") (pintype "bidirectional"))
    )
    (net (code "58") (name "unconnected-(J1-EP-Pad9)") (class "Default")
      (node (ref "J1") (pin "9") (pinfunction "EP_9") (pintype "bidirectional"))
    )
    (net (code "59") (name "unconnected-(J4-Pad6)") (class "Default")
      (node (ref "J4") (pin "6") (pinfunction "6_6") (pintype "passive"))
    )
    (net (code "60") (name "unconnected-(NUCLEO_STM32-BOOT0-Pad31)") (class "Default")
      (node (ref "NUCLEO_STM32") (pin "31") (pinfunction "BOOT0_31") (pintype "bidirectional"))
    )
    (net (code "61") (name "unconnected-(NUCLEO_STM32-PA0-CK_IN-Pad6)") (class "Default")
      (node (ref "NUCLEO_STM32") (pin "6") (pinfunction "PA0-CK_IN_6") (pintype "bidirectional"))
    )
    (net (code "62") (name "unconnected-(NUCLEO_STM32-PA1-Pad7)") (class "Default")
      (node (ref "NUCLEO_STM32") (pin "7") (pinfunction "PA1_7") (pintype "bidirectional"))
    )
    (net (code "63") (name "unconnected-(NUCLEO_STM32-PA2-Pad8)") (class "Default")
      (node (ref "NUCLEO_STM32") (pin "8") (pinfunction "PA2_8") (pintype "bidirectional"))
    )
    (net (code "64") (name "unconnected-(NUCLEO_STM32-PA3-Pad9)") (class "Default")
      (node (ref "NUCLEO_STM32") (pin "9") (pinfunction "PA3_9") (pintype "bidirectional"))
    )
    (net (code "65") (name "unconnected-(NUCLEO_STM32-PA4-Pad10)") (class "Default")
      (node (ref "NUCLEO_STM32") (pin "10") (pinfunction "PA4_10") (pintype "bidirectional"))
    )
    (net (code "66") (name "unconnected-(NUCLEO_STM32-PA6-Pad12)") (class "Default")
      (node (ref "NUCLEO_STM32") (pin "12") (pinfunction "PA6_12") (pintype "bidirectional"))
    )
    (net (code "67") (name "unconnected-(NUCLEO_STM32-PA7-Pad13)") (class "Default")
      (node (ref "NUCLEO_STM32") (pin "13") (pinfunction "PA7_13") (pintype "bidirectional"))
    )
    (net (code "68") (name "unconnected-(NUCLEO_STM32-PA8-Pad18)") (class "Default")
      (node (ref "NUCLEO_STM32") (pin "18") (pinfunction "PA8_18") (pintype "bidirectional"))
    )
    (net (code "69") (name "unconnected-(NUCLEO_STM32-PA11-Pad21)") (class "Default")
      (node (ref "NUCLEO_STM32") (pin "21") (pinfunction "PA11_21") (pintype "bidirectional"))
    )
    (net (code "70") (name "unconnected-(NUCLEO_STM32-PA12-Pad22)") (class "Default")
      (node (ref "NUCLEO_STM32") (pin "22") (pinfunction "PA12_22") (pintype "bidirectional"))
    )
    (net (code "71") (name "unconnected-(NUCLEO_STM32-PA15-Pad25)") (class "Default")
      (node (ref "NUCLEO_STM32") (pin "25") (pinfunction "PA15_25") (pintype "bidirectional"))
    )
    (net (code "72") (name "unconnected-(NUCLEO_STM32-PB0-Pad14)") (class "Default")
      (node (ref "NUCLEO_STM32") (pin "14") (pinfunction "PB0_14") (pintype "bidirectional"))
    )
    (net (code "73") (name "unconnected-(NUCLEO_STM32-PB4-Pad27)") (class "Default")
      (node (ref "NUCLEO_STM32") (pin "27") (pinfunction "PB4_27") (pintype "bidirectional"))
    )
    (net (code "74") (name "unconnected-(NUCLEO_STM32-PB5-Pad28)") (class "Default")
      (node (ref "NUCLEO_STM32") (pin "28") (pinfunction "PB5_28") (pintype "bidirectional"))
    )
    (net (code "75") (name "unconnected-(U1-D+-PadD+1)") (class "Default")
      (node (ref "U1") (pin "D+1") (pinfunction "D+_D+1") (pintype "bidirectional"))
    )
    (net (code "76") (name "unconnected-(U1-D--PadD-1)") (class "Default")
      (node (ref "U1") (pin "D-1") (pinfunction "D-_D-1") (pintype "bidirectional"))
    )
    (net (code "77") (name "unconnected-(U1-USBID-PadID1)") (class "Default")
      (node (ref "U1") (pin "ID1") (pinfunction "USBID_ID1") (pintype "bidirectional"))
    )
  )
)
